# HEATER.net
KiCad netlist of a schematic drawn in Altium Designer
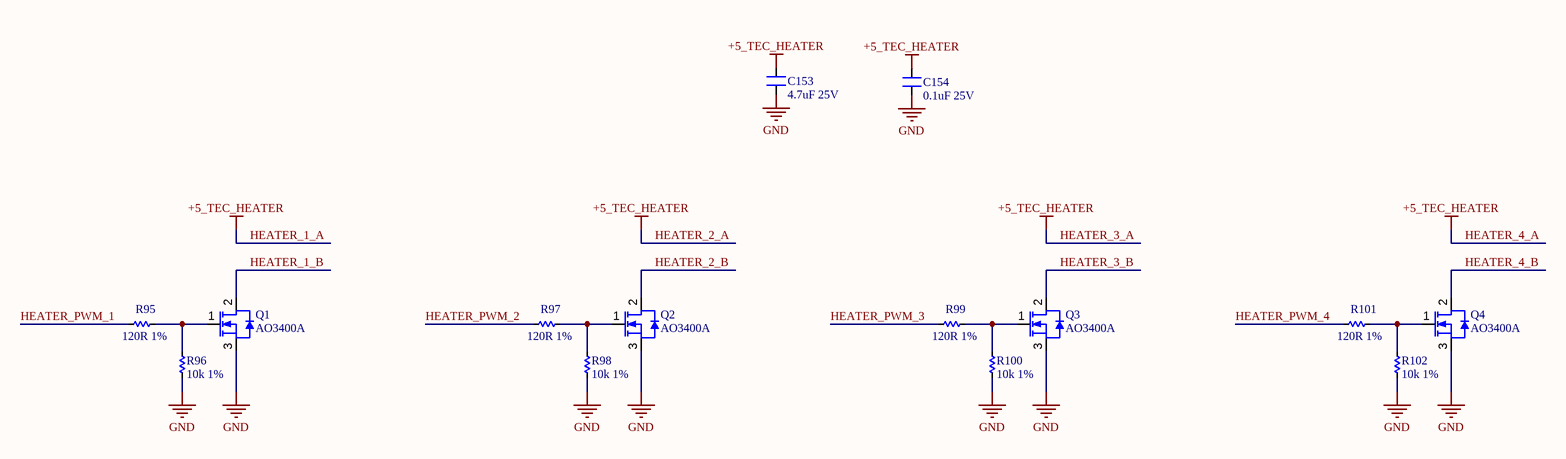
[diagram p0: HEATER.SchDoc]

(export (version "E")
  (design (tool "Eeschema 10.0.6"))
  (components
    (comp (ref "C153")
      (value "4.7uF 25V")
      (footprint "CN-SMD-0603-EXP-V101")
      (libsource (lib "Sang_library") (part "Capacitors"))
    )
    (comp (ref "C154")
      (value "0.1uF 25V")
      (footprint "CN-SMD-0603-EXP-V101")
      (libsource (lib "Sang_library") (part "Capacitors"))
    )
    (comp (ref "Q1")
      (value "AO3400A")
      (footprint "SOT23-13_2")
      (description "MOSFET N-CH 30V 5.7A SOT23-3L")
      (libsource (lib "Sang_library") (part "AO3400A"))
    )
    (comp (ref "Q2")
      (value "AO3400A")
      (footprint "SOT23-13_2")
      (description "MOSFET N-CH 30V 5.7A SOT23-3L")
      (libsource (lib "Sang_library") (part "AO3400A"))
    )
    (comp (ref "Q3")
      (value "AO3400A")
      (footprint "SOT23-13_2")
      (description "MOSFET N-CH 30V 5.7A SOT23-3L")
      (libsource (lib "Sang_library") (part "AO3400A"))
    )
    (comp (ref "Q4")
      (value "AO3400A")
      (footprint "SOT23-13_2")
      (description "MOSFET N-CH 30V 5.7A SOT23-3L")
      (libsource (lib "Sang_library") (part "AO3400A"))
    )
    (comp (ref "R95")
      (value "120R 1%")
      (footprint "RES-SMD-0603-EXP-V101")
      (description "SMD")
      (fields
        (field (name "MANUFACTURER") "Generic Components")
        (field (name "PUBLISHER") "Altium Hobart Technology Centre")
      )
      (libsource (lib "Sang_library") (part "Res SMD"))
    )
    (comp (ref "R96")
      (value "10k 1%")
      (footprint "RES-SMD-0603-EXP-V101")
      (description "SMD")
      (fields
        (field (name "MANUFACTURER") "Generic Components")
        (field (name "PUBLISHER") "Altium Hobart Technology Centre")
      )
      (libsource (lib "Sang_library") (part "Res SMD"))
    )
    (comp (ref "R97")
      (value "120R 1%")
      (footprint "RES-SMD-0603-EXP-V101")
      (description "SMD")
      (fields
        (field (name "MANUFACTURER") "Generic Components")
        (field (name "PUBLISHER") "Altium Hobart Technology Centre")
      )
      (libsource (lib "Sang_library") (part "Res SMD"))
    )
    (comp (ref "R98")
      (value "10k 1%")
      (footprint "RES-SMD-0603-EXP-V101")
      (description "SMD")
      (fields
        (field (name "MANUFACTURER") "Generic Components")
        (field (name "PUBLISHER") "Altium Hobart Technology Centre")
      )
      (libsource (lib "Sang_library") (part "Res SMD"))
    )
    (comp (ref "R99")
      (value "120R 1%")
      (footprint "RES-SMD-0603-EXP-V101")
      (description "SMD")
      (fields
        (field (name "MANUFACTURER") "Generic Components")
        (field (name "PUBLISHER") "Altium Hobart Technology Centre")
      )
      (libsource (lib "Sang_library") (part "Res SMD"))
    )
    (comp (ref "R100")
      (value "10k 1%")
      (footprint "RES-SMD-0603-EXP-V101")
      (description "SMD")
      (fields
        (field (name "MANUFACTURER") "Generic Components")
        (field (name "PUBLISHER") "Altium Hobart Technology Centre")
      )
      (libsource (lib "Sang_library") (part "Res SMD"))
    )
    (comp (ref "R101")
      (value "120R 1%")
      (footprint "RES-SMD-0603-EXP-V101")
      (description "SMD")
      (fields
        (field (name "MANUFACTURER") "Generic Components")
        (field (name "PUBLISHER") "Altium Hobart Technology Centre")
      )
      (libsource (lib "Sang_library") (part "Res SMD"))
    )
    (comp (ref "R102")
      (value "10k 1%")
      (footprint "RES-SMD-0603-EXP-V101")
      (description "SMD")
      (fields
        (field (name "MANUFACTURER") "Generic Components")
        (field (name "PUBLISHER") "Altium Hobart Technology Centre")
      )
      (libsource (lib "Sang_library") (part "Res SMD"))
    )
  )
  (nets
    (net (code "1") (name "+5_TEC_HEATER") (class "Default")
      (node (ref "C153") (pin "2") (pinfunction "2_2") (pintype "passive"))
      (node (ref "C154") (pin "2") (pinfunction "2_2") (pintype "passive"))
    )
    (net (code "2") (name "/HEATER_1_B") (class "Default")
      (node (ref "Q1") (pin "2") (pinfunction "D_2") (pintype "passive"))
    )
    (net (code "3") (name "/HEATER_2_B") (class "Default")
      (node (ref "Q2") (pin "2") (pinfunction "D_2") (pintype "passive"))
    )
    (net (code "4") (name "/HEATER_3_B") (class "Default")
      (node (ref "Q3") (pin "2") (pinfunction "D_2") (pintype "passive"))
    )
    (net (code "5") (name "/HEATER_4_B") (class "Default")
      (node (ref "Q4") (pin "2") (pinfunction "D_2") (pintype "passive"))
    )
    (net (code "6") (name "/HEATER_PWM_1") (class "Default")
      (node (ref "R95") (pin "1") (pinfunction "1_1") (pintype "passive"))
    )
    (net (code "7") (name "/HEATER_PWM_2") (class "Default")
      (node (ref "R97") (pin "1") (pinfunction "1_1") (pintype "passive"))
    )
    (net (code "8") (name "/HEATER_PWM_3") (class "Default")
      (node (ref "R99") (pin "1") (pinfunction "1_1") (pintype "passive"))
    )
    (net (code "9") (name "/HEATER_PWM_4") (class "Default")
      (node (ref "R101") (pin "1") (pinfunction "1_1") (pintype "passive"))
    )
    (net (code "10") (name "GND") (class "Default")
      (node (ref "C153") (pin "1") (pinfunction "1_1") (pintype "passive"))
      (node (ref "C154") (pin "1") (pinfunction "1_1") (pintype "passive"))
      (node (ref "Q1") (pin "3") (pinfunction "S_3") (pintype "passive"))
      (node (ref "Q2") (pin "3") (pinfunction "S_3") (pintype "passive"))
      (node (ref "Q3") (pin "3") (pinfunction "S_3") (pintype "passive"))
      (node (ref "Q4") (pin "3") (pinfunction "S_3") (pintype "passive"))
      (node (ref "R100") (pin "1") (pinfunction "1_1") (pintype "passive"))
      (node (ref "R102") (pin "1") (pinfunction "1_1") (pintype "passive"))
      (node (ref "R96") (pin "1") (pinfunction "1_1") (pintype "passive"))
      (node (ref "R98") (pin "1") (pinfunction "1_1") (pintype "passive"))
    )
    (net (code "11") (name "Net-(Q1-G)") (class "Default")
      (node (ref "Q1") (pin "1") (pinfunction "G_1") (pintype "passive"))
      (node (ref "R95") (pin "2") (pinfunction "2_2") (pintype "passive"))
      (node (ref "R96") (pin "2") (pinfunction "2_2") (pintype "passive"))
    )
    (net (code "12") (name "Net-(Q2-G)") (class "Default")
      (node (ref "Q2") (pin "1") (pinfunction "G_1") (pintype "passive"))
      (node (ref "R97") (pin "2") (pinfunction "2_2") (pintype "passive"))
      (node (ref "R98") (pin "2") (pinfunction "2_2") (pintype "passive"))
    )
    (net (code "13") (name "Net-(Q3-G)") (class "Default")
      (node (ref "Q3") (pin "1") (pinfunction "G_1") (pintype "passive"))
      (node (ref "R100") (pin "2") (pinfunction "2_2") (pintype "passive"))
      (node (ref "R99") (pin "2") (pinfunction "2_2") (pintype "passive"))
    )
    (net (code "14") (name "Net-(Q4-G)") (class "Default")
      (node (ref "Q4") (pin "1") (pinfunction "G_1") (pintype "passive"))
      (node (ref "R101") (pin "2") (pinfunction "2_2") (pintype "passive"))
      (node (ref "R102") (pin "2") (pinfunction "2_2") (pintype "passive"))
    )
  )
)
